# 2_MCU.net
KiCad netlist of a schematic drawn in Altium Designer
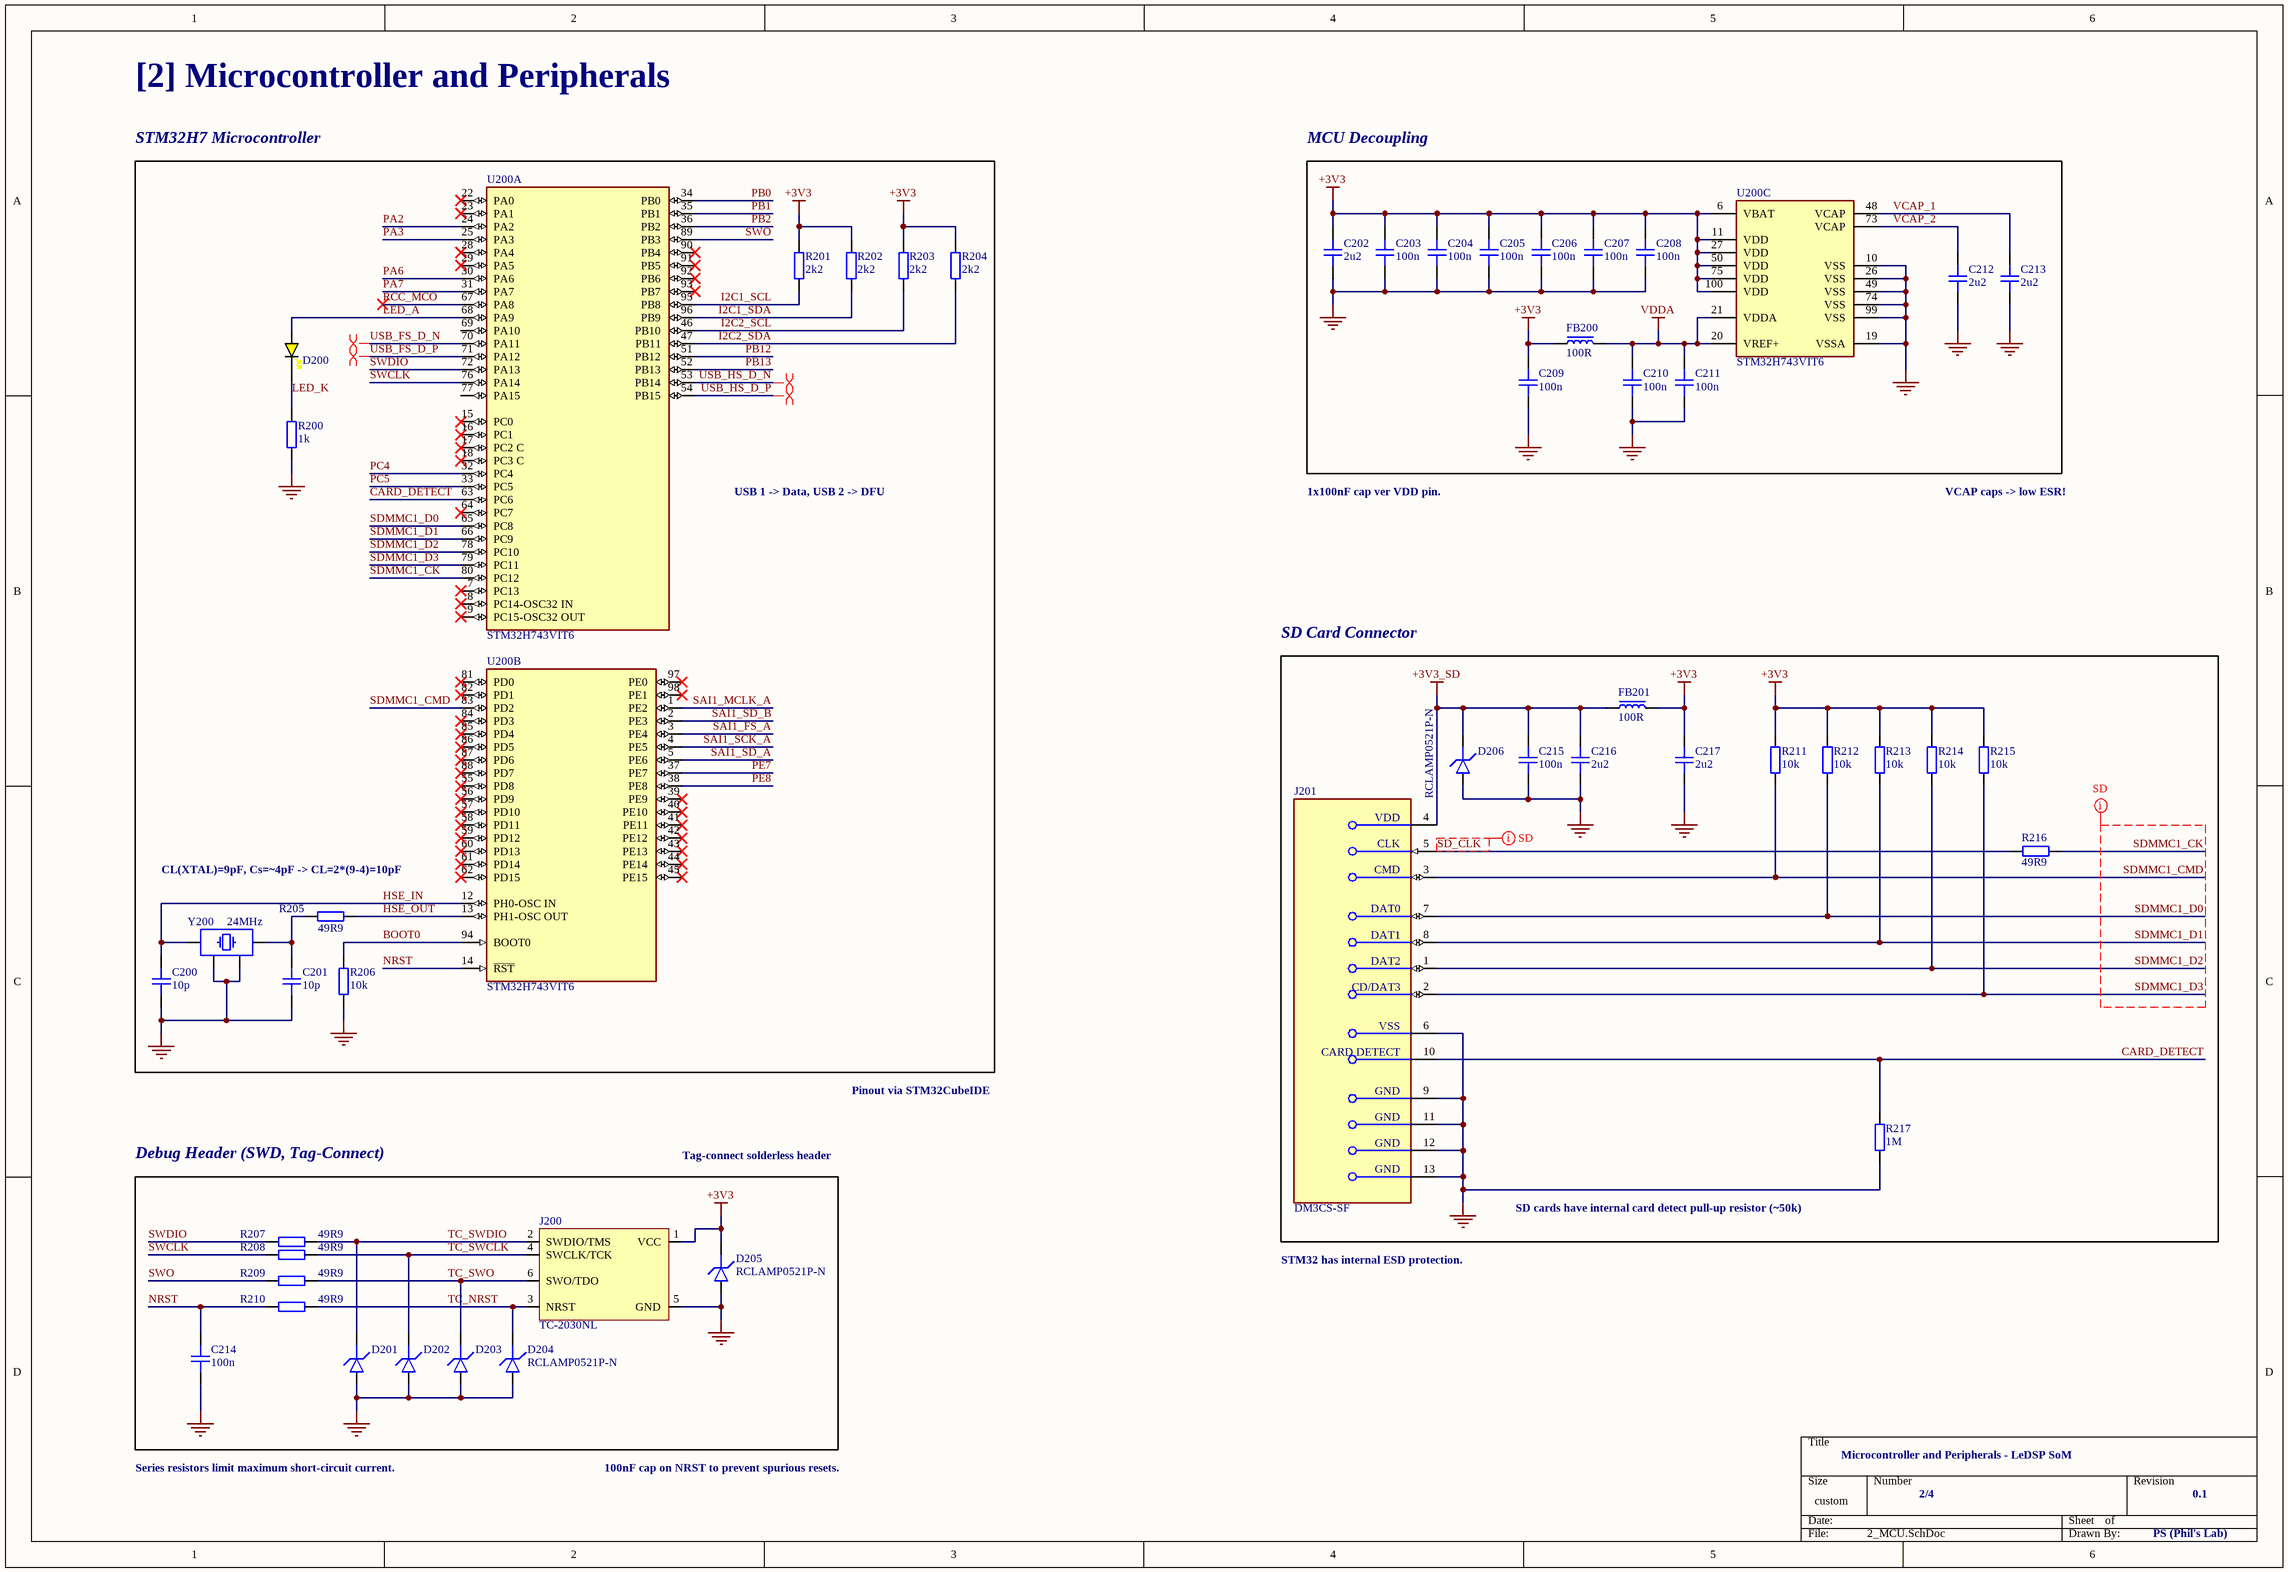
[diagram p0: 2_MCU.SchDoc]

(export (version "E")
  (design (tool "Eeschema 10.0.6"))
  (components
    (comp (ref "C200")
      (value "10p")
      (footprint "CAP_0402")
      (description "Capacitor SMD 0402 16V")
      (libsource (lib "Schematic-Lib-PhilsLab") (part "CAP_0402_16V"))
    )
    (comp (ref "C201")
      (value "10p")
      (footprint "CAP_0402")
      (description "Capacitor SMD 0402 16V")
      (libsource (lib "Schematic-Lib-PhilsLab") (part "CAP_0402_16V"))
    )
    (comp (ref "C202")
      (value "2u2")
      (footprint "CAP_0603")
      (description "Capacitor SMD 0603 16V")
      (libsource (lib "Schematic-Lib-PhilsLab") (part "CAP_0603_16V"))
    )
    (comp (ref "C203")
      (value "100n")
      (footprint "CAP_0402")
      (description "Capacitor SMD 0402 16V")
      (libsource (lib "Schematic-Lib-PhilsLab") (part "CAP_0402_16V"))
    )
    (comp (ref "C204")
      (value "100n")
      (footprint "CAP_0402")
      (description "Capacitor SMD 0402 16V")
      (libsource (lib "Schematic-Lib-PhilsLab") (part "CAP_0402_16V"))
    )
    (comp (ref "C205")
      (value "100n")
      (footprint "CAP_0402")
      (description "Capacitor SMD 0402 16V")
      (libsource (lib "Schematic-Lib-PhilsLab") (part "CAP_0402_16V"))
    )
    (comp (ref "C206")
      (value "100n")
      (footprint "CAP_0402")
      (description "Capacitor SMD 0402 16V")
      (libsource (lib "Schematic-Lib-PhilsLab") (part "CAP_0402_16V"))
    )
    (comp (ref "C207")
      (value "100n")
      (footprint "CAP_0402")
      (description "Capacitor SMD 0402 16V")
      (libsource (lib "Schematic-Lib-PhilsLab") (part "CAP_0402_16V"))
    )
    (comp (ref "C208")
      (value "100n")
      (footprint "CAP_0402")
      (description "Capacitor SMD 0402 16V")
      (libsource (lib "Schematic-Lib-PhilsLab") (part "CAP_0402_16V"))
    )
    (comp (ref "C209")
      (value "100n")
      (footprint "CAP_0402")
      (description "Capacitor SMD 0402 16V")
      (libsource (lib "Schematic-Lib-PhilsLab") (part "CAP_0402_16V"))
    )
    (comp (ref "C210")
      (value "100n")
      (footprint "CAP_0402")
      (description "Capacitor SMD 0402 16V")
      (libsource (lib "Schematic-Lib-PhilsLab") (part "CAP_0402_16V"))
    )
    (comp (ref "C211")
      (value "100n")
      (footprint "CAP_0402")
      (description "Capacitor SMD 0402 16V")
      (libsource (lib "Schematic-Lib-PhilsLab") (part "CAP_0402_16V"))
    )
    (comp (ref "C212")
      (value "2u2")
      (footprint "CAP_0402")
      (description "Capacitor SMD 0402 16V")
      (libsource (lib "Schematic-Lib-PhilsLab") (part "CAP_0402_16V"))
    )
    (comp (ref "C213")
      (value "2u2")
      (footprint "CAP_0402")
      (description "Capacitor SMD 0402 16V")
      (libsource (lib "Schematic-Lib-PhilsLab") (part "CAP_0402_16V"))
    )
    (comp (ref "C214")
      (value "100n")
      (footprint "CAP_0402")
      (description "Capacitor SMD 0402 16V")
      (libsource (lib "Schematic-Lib-PhilsLab") (part "CAP_0402_16V"))
    )
    (comp (ref "C215")
      (value "100n")
      (footprint "CAP_0402")
      (description "Capacitor SMD 0402 16V")
      (libsource (lib "Schematic-Lib-PhilsLab") (part "CAP_0402_16V"))
    )
    (comp (ref "C216")
      (value "2u2")
      (footprint "CAP_0603")
      (description "Capacitor SMD 0603 16V")
      (libsource (lib "Schematic-Lib-PhilsLab") (part "CAP_0603_16V"))
    )
    (comp (ref "C217")
      (value "2u2")
      (footprint "CAP_0603")
      (description "Capacitor SMD 0603 16V")
      (libsource (lib "Schematic-Lib-PhilsLab") (part "CAP_0603_16V"))
    )
    (comp (ref "D200")
      (value "YELLOW")
      (footprint "LED_0402_YELLOW")
      (description "LED 0402 YELLOW SMD")
      (libsource (lib "Schematic-Lib-PhilsLab") (part "LED_0402_YELLOW"))
    )
    (comp (ref "D201")
      (value "RCLAMP0521P-N")
      (footprint "D_0402")
      (description "Diode TVS / ESD 0402")
      (libsource (lib "Schematic-Lib-PhilsLab") (part "D_TVS_0402"))
    )
    (comp (ref "D202")
      (value "RCLAMP0521P-N")
      (footprint "D_0402")
      (description "Diode TVS / ESD 0402")
      (libsource (lib "Schematic-Lib-PhilsLab") (part "D_TVS_0402"))
    )
    (comp (ref "D203")
      (value "RCLAMP0521P-N")
      (footprint "D_0402")
      (description "Diode TVS / ESD 0402")
      (libsource (lib "Schematic-Lib-PhilsLab") (part "D_TVS_0402"))
    )
    (comp (ref "D204")
      (value "RCLAMP0521P-N")
      (footprint "D_0402")
      (description "Diode TVS / ESD 0402")
      (libsource (lib "Schematic-Lib-PhilsLab") (part "D_TVS_0402"))
    )
    (comp (ref "D205")
      (value "RCLAMP0521P-N")
      (footprint "D_0402")
      (description "Diode TVS / ESD 0402")
      (libsource (lib "Schematic-Lib-PhilsLab") (part "D_TVS_0402"))
    )
    (comp (ref "D206")
      (value "RCLAMP0521P-N")
      (footprint "D_0402")
      (description "Diode TVS / ESD 0402")
      (libsource (lib "Schematic-Lib-PhilsLab") (part "D_TVS_0402"))
    )
    (comp (ref "FB200")
      (value "100R")
      (footprint "FB_0603")
      (description "Ferrite Bead SMD 0603")
      (libsource (lib "Schematic-Lib-PhilsLab") (part "FB_0603"))
    )
    (comp (ref "FB201")
      (value "100R")
      (footprint "FB_0603")
      (description "Ferrite Bead SMD 0603")
      (libsource (lib "Schematic-Lib-PhilsLab") (part "FB_0603"))
    )
    (comp (ref "J200")
      (value "TC-2030NL")
      (footprint "TC2030-NL-FP")
      (description "Tag-Connect No-Solder SWD Debug Connector (No Legs) DO NOT PLACE")
      (fields (field (name "MANUFACTURER") "Tag-Connect"))
      (libsource (lib "Schematic-Lib-PhilsLab") (part "TC2030-NL"))
    )
    (comp (ref "J201")
      (value "DM3CS-SF")
      (footprint "FP-DM3CS-SF-MFG")
      (description "CONN MICRO SD CARD HINGED TYPE")
      (libsource (lib "Altium Content Vault") (part "bac915de5305cfdd1ca301aae530106"))
    )
    (comp (ref "R200")
      (value "1k")
      (footprint "RES_0402")
      (description "Resistor SMD 0402")
      (libsource (lib "Schematic-Lib-PhilsLab") (part "RES_0402"))
    )
    (comp (ref "R201")
      (value "2k2")
      (footprint "RES_0402")
      (description "Resistor SMD 0402")
      (libsource (lib "Schematic-Lib-PhilsLab") (part "RES_0402"))
    )
    (comp (ref "R202")
      (value "2k2")
      (footprint "RES_0402")
      (description "Resistor SMD 0402")
      (libsource (lib "Schematic-Lib-PhilsLab") (part "RES_0402"))
    )
    (comp (ref "R203")
      (value "2k2")
      (footprint "RES_0402")
      (description "Resistor SMD 0402")
      (libsource (lib "Schematic-Lib-PhilsLab") (part "RES_0402"))
    )
    (comp (ref "R204")
      (value "2k2")
      (footprint "RES_0402")
      (description "Resistor SMD 0402")
      (libsource (lib "Schematic-Lib-PhilsLab") (part "RES_0402"))
    )
    (comp (ref "R205")
      (value "49R9")
      (footprint "RES_0402")
      (description "Resistor SMD 0402")
      (libsource (lib "Schematic-Lib-PhilsLab") (part "RES_0402"))
    )
    (comp (ref "R206")
      (value "10k")
      (footprint "RES_0402")
      (description "Resistor SMD 0402")
      (libsource (lib "Schematic-Lib-PhilsLab") (part "RES_0402"))
    )
    (comp (ref "R207")
      (value "49R9")
      (footprint "RES_0402")
      (description "Resistor SMD 0402")
      (libsource (lib "Schematic-Lib-PhilsLab") (part "RES_0402"))
    )
    (comp (ref "R208")
      (value "49R9")
      (footprint "RES_0402")
      (description "Resistor SMD 0402")
      (libsource (lib "Schematic-Lib-PhilsLab") (part "RES_0402"))
    )
    (comp (ref "R209")
      (value "49R9")
      (footprint "RES_0402")
      (description "Resistor SMD 0402")
      (libsource (lib "Schematic-Lib-PhilsLab") (part "RES_0402"))
    )
    (comp (ref "R210")
      (value "49R9")
      (footprint "RES_0402")
      (description "Resistor SMD 0402")
      (libsource (lib "Schematic-Lib-PhilsLab") (part "RES_0402"))
    )
    (comp (ref "R211")
      (value "10k")
      (footprint "RES_0402")
      (description "Resistor SMD 0402")
      (libsource (lib "Schematic-Lib-PhilsLab") (part "RES_0402"))
    )
    (comp (ref "R212")
      (value "10k")
      (footprint "RES_0402")
      (description "Resistor SMD 0402")
      (libsource (lib "Schematic-Lib-PhilsLab") (part "RES_0402"))
    )
    (comp (ref "R213")
      (value "10k")
      (footprint "RES_0402")
      (description "Resistor SMD 0402")
      (libsource (lib "Schematic-Lib-PhilsLab") (part "RES_0402"))
    )
    (comp (ref "R214")
      (value "10k")
      (footprint "RES_0402")
      (description "Resistor SMD 0402")
      (libsource (lib "Schematic-Lib-PhilsLab") (part "RES_0402"))
    )
    (comp (ref "R215")
      (value "10k")
      (footprint "RES_0402")
      (description "Resistor SMD 0402")
      (libsource (lib "Schematic-Lib-PhilsLab") (part "RES_0402"))
    )
    (comp (ref "R216")
      (value "49R9")
      (footprint "RES_0402")
      (description "Resistor SMD 0402")
      (libsource (lib "Schematic-Lib-PhilsLab") (part "RES_0402"))
    )
    (comp (ref "R217")
      (value "1M")
      (footprint "RES_0402")
      (description "Resistor SMD 0402")
      (libsource (lib "Schematic-Lib-PhilsLab") (part "RES_0402"))
    )
    (comp (ref "U200")
      (value "STM32H743VIT6")
      (footprint "FP-LQFP100-1L-MFG")
      (description "IC MCU 32BIT 2MB FLASH 100LQFP")
      (fields
        (field (name "OCTOPART") "https://octopart.com/stm32h743vit6-stmicroelectronics-76372527")
        (field (name "MANUFACTURER") "STMicroelectronics")
      )
      (libsource (lib "Altium Content Vault") (part "01082ce2885d1d16a22823c45526fe6"))
    )
    (comp (ref "Y200")
      (value "24MHz")
      (footprint "XTAL_3225")
      (description "Crystal SMD 24MHz 10PPM 7pF 3225")
      (fields (field (name "MANUFACTURER") "Epson"))
      (libsource (lib "Schematic-Lib-PhilsLab") (part "TSX-3225_24.0000MF15X-AC"))
    )
  )
  (nets
    (net (code "1") (name "+3V3") (class "Default")
      (node (ref "C202") (pin "2") (pinfunction "2_2") (pintype "passive"))
      (node (ref "C203") (pin "2") (pinfunction "2_2") (pintype "passive"))
      (node (ref "C204") (pin "2") (pinfunction "2_2") (pintype "passive"))
      (node (ref "C205") (pin "2") (pinfunction "2_2") (pintype "passive"))
      (node (ref "C206") (pin "2") (pinfunction "2_2") (pintype "passive"))
      (node (ref "C207") (pin "2") (pinfunction "2_2") (pintype "passive"))
      (node (ref "C208") (pin "2") (pinfunction "2_2") (pintype "passive"))
      (node (ref "C209") (pin "2") (pinfunction "2_2") (pintype "passive"))
      (node (ref "C217") (pin "2") (pinfunction "2_2") (pintype "passive"))
      (node (ref "D205") (pin "K") (pinfunction "K_K") (pintype "passive"))
      (node (ref "FB200") (pin "1") (pinfunction "1_1") (pintype "passive"))
      (node (ref "FB201") (pin "2") (pinfunction "2_2") (pintype "passive"))
      (node (ref "J200") (pin "1") (pinfunction "VCC_1") (pintype "passive"))
      (node (ref "R201") (pin "2") (pinfunction "2_2") (pintype "passive"))
      (node (ref "R202") (pin "2") (pinfunction "2_2") (pintype "passive"))
      (node (ref "R203") (pin "2") (pinfunction "2_2") (pintype "passive"))
      (node (ref "R204") (pin "2") (pinfunction "2_2") (pintype "passive"))
      (node (ref "R211") (pin "2") (pinfunction "2_2") (pintype "passive"))
      (node (ref "R212") (pin "2") (pinfunction "2_2") (pintype "passive"))
      (node (ref "R213") (pin "2") (pinfunction "2_2") (pintype "passive"))
      (node (ref "R214") (pin "2") (pinfunction "2_2") (pintype "passive"))
      (node (ref "R215") (pin "2") (pinfunction "2_2") (pintype "passive"))
      (node (ref "U200") (pin "100") (pinfunction "VDD_100") (pintype "power_in"))
      (node (ref "U200") (pin "11") (pinfunction "VDD_11") (pintype "power_in"))
      (node (ref "U200") (pin "27") (pinfunction "VDD_27") (pintype "power_in"))
      (node (ref "U200") (pin "50") (pinfunction "VDD_50") (pintype "power_in"))
      (node (ref "U200") (pin "6") (pinfunction "VBAT_6") (pintype "power_in"))
      (node (ref "U200") (pin "75") (pinfunction "VDD_75") (pintype "power_in"))
    )
    (net (code "2") (name "+3V3_SD") (class "Default")
      (node (ref "C215") (pin "2") (pinfunction "2_2") (pintype "passive"))
      (node (ref "C216") (pin "2") (pinfunction "2_2") (pintype "passive"))
      (node (ref "D206") (pin "K") (pinfunction "K_K") (pintype "passive"))
      (node (ref "FB201") (pin "1") (pinfunction "1_1") (pintype "passive"))
      (node (ref "J201") (pin "4") (pinfunction "VDD_4") (pintype "power_in"))
    )
    (net (code "3") (name "/BOOT0") (class "Default")
      (node (ref "R206") (pin "2") (pinfunction "2_2") (pintype "passive"))
      (node (ref "U200") (pin "94") (pinfunction "BOOT0_94") (pintype "input"))
    )
    (net (code "4") (name "/CARD_DETECT") (class "Default")
      (node (ref "J201") (pin "10") (pinfunction "CARD_DETECT_10") (pintype "passive"))
      (node (ref "R217") (pin "2") (pinfunction "2_2") (pintype "passive"))
      (node (ref "U200") (pin "63") (pinfunction "PC6_63") (pintype "bidirectional"))
    )
    (net (code "5") (name "/HSE_IN") (class "Default")
      (node (ref "C200") (pin "2") (pinfunction "2_2") (pintype "passive"))
      (node (ref "U200") (pin "12") (pinfunction "PH0-OSC_IN_12") (pintype "bidirectional"))
      (node (ref "Y200") (pin "1") (pinfunction "1_1") (pintype "passive"))
    )
    (net (code "6") (name "/HSE_OUT") (class "Default")
      (node (ref "R205") (pin "2") (pinfunction "2_2") (pintype "passive"))
      (node (ref "U200") (pin "13") (pinfunction "PH1-OSC_OUT_13") (pintype "bidirectional"))
    )
    (net (code "7") (name "/I2C1_SCL") (class "Default")
      (node (ref "R201") (pin "1") (pinfunction "1_1") (pintype "passive"))
      (node (ref "U200") (pin "95") (pinfunction "PB8_95") (pintype "bidirectional"))
    )
    (net (code "8") (name "/I2C1_SDA") (class "Default")
      (node (ref "R202") (pin "1") (pinfunction "1_1") (pintype "passive"))
      (node (ref "U200") (pin "96") (pinfunction "PB9_96") (pintype "bidirectional"))
    )
    (net (code "9") (name "/I2C2_SCL") (class "Default")
      (node (ref "R203") (pin "1") (pinfunction "1_1") (pintype "passive"))
      (node (ref "U200") (pin "46") (pinfunction "PB10_46") (pintype "bidirectional"))
    )
    (net (code "10") (name "/I2C2_SDA") (class "Default")
      (node (ref "R204") (pin "1") (pinfunction "1_1") (pintype "passive"))
      (node (ref "U200") (pin "47") (pinfunction "PB11_47") (pintype "bidirectional"))
    )
    (net (code "11") (name "/LED_A") (class "Default")
      (node (ref "D200") (pin "A") (pinfunction "A_A") (pintype "passive"))
      (node (ref "U200") (pin "68") (pinfunction "PA9_68") (pintype "bidirectional"))
    )
    (net (code "12") (name "/LED_K") (class "Default")
      (node (ref "D200") (pin "K") (pinfunction "K_K") (pintype "passive"))
      (node (ref "R200") (pin "2") (pinfunction "2_2") (pintype "passive"))
    )
    (net (code "13") (name "/NRST") (class "Default")
      (node (ref "C214") (pin "2") (pinfunction "2_2") (pintype "passive"))
      (node (ref "R210") (pin "1") (pinfunction "1_1") (pintype "passive"))
      (node (ref "U200") (pin "14") (pinfunction "~{RST}_14") (pintype "input"))
    )
    (net (code "14") (name "/PA2") (class "Default")
      (node (ref "U200") (pin "24") (pinfunction "PA2_24") (pintype "bidirectional"))
    )
    (net (code "15") (name "/PA3") (class "Default")
      (node (ref "U200") (pin "25") (pinfunction "PA3_25") (pintype "bidirectional"))
    )
    (net (code "16") (name "/PA6") (class "Default")
      (node (ref "U200") (pin "30") (pinfunction "PA6_30") (pintype "bidirectional"))
    )
    (net (code "17") (name "/PA7") (class "Default")
      (node (ref "U200") (pin "31") (pinfunction "PA7_31") (pintype "bidirectional"))
    )
    (net (code "18") (name "/PB0") (class "Default")
      (node (ref "U200") (pin "34") (pinfunction "PB0_34") (pintype "bidirectional"))
    )
    (net (code "19") (name "/PB1") (class "Default")
      (node (ref "U200") (pin "35") (pinfunction "PB1_35") (pintype "bidirectional"))
    )
    (net (code "20") (name "/PB2") (class "Default")
      (node (ref "U200") (pin "36") (pinfunction "PB2_36") (pintype "bidirectional"))
    )
    (net (code "21") (name "/PB12") (class "Default")
      (node (ref "U200") (pin "51") (pinfunction "PB12_51") (pintype "bidirectional"))
    )
    (net (code "22") (name "/PB13") (class "Default")
      (node (ref "U200") (pin "52") (pinfunction "PB13_52") (pintype "bidirectional"))
    )
    (net (code "23") (name "/PC4") (class "Default")
      (node (ref "U200") (pin "32") (pinfunction "PC4_32") (pintype "bidirectional"))
    )
    (net (code "24") (name "/PC5") (class "Default")
      (node (ref "U200") (pin "33") (pinfunction "PC5_33") (pintype "bidirectional"))
    )
    (net (code "25") (name "/PE7") (class "Default")
      (node (ref "U200") (pin "37") (pinfunction "PE7_37") (pintype "bidirectional"))
    )
    (net (code "26") (name "/PE8") (class "Default")
      (node (ref "U200") (pin "38") (pinfunction "PE8_38") (pintype "bidirectional"))
    )
    (net (code "27") (name "/RCC_MCO") (class "Default")
      (node (ref "U200") (pin "67") (pinfunction "PA8_67") (pintype "bidirectional+no_connect"))
    )
    (net (code "28") (name "/SAI1_FS_A") (class "Default")
      (node (ref "U200") (pin "3") (pinfunction "PE4_3") (pintype "bidirectional"))
    )
    (net (code "29") (name "/SAI1_MCLK_A") (class "Default")
      (node (ref "U200") (pin "1") (pinfunction "PE2_1") (pintype "bidirectional"))
    )
    (net (code "30") (name "/SAI1_SCK_A") (class "Default")
      (node (ref "U200") (pin "4") (pinfunction "PE5_4") (pintype "bidirectional"))
    )
    (net (code "31") (name "/SAI1_SD_A") (class "Default")
      (node (ref "U200") (pin "5") (pinfunction "PE6_5") (pintype "bidirectional"))
    )
    (net (code "32") (name "/SAI1_SD_B") (class "Default")
      (node (ref "U200") (pin "2") (pinfunction "PE3_2") (pintype "bidirectional"))
    )
    (net (code "33") (name "/SDMMC1_CK") (class "Default")
      (node (ref "R216") (pin "2") (pinfunction "2_2") (pintype "passive"))
      (node (ref "U200") (pin "80") (pinfunction "PC12_80") (pintype "bidirectional"))
    )
    (net (code "34") (name "/SDMMC1_CMD") (class "Default")
      (node (ref "J201") (pin "3") (pinfunction "CMD_3") (pintype "bidirectional"))
      (node (ref "R211") (pin "1") (pinfunction "1_1") (pintype "passive"))
      (node (ref "U200") (pin "83") (pinfunction "PD2_83") (pintype "bidirectional"))
    )
    (net (code "35") (name "/SDMMC1_D0") (class "Default")
      (node (ref "J201") (pin "7") (pinfunction "DAT0_7") (pintype "bidirectional"))
      (node (ref "R212") (pin "1") (pinfunction "1_1") (pintype "passive"))
      (node (ref "U200") (pin "65") (pinfunction "PC8_65") (pintype "bidirectional"))
    )
    (net (code "36") (name "/SDMMC1_D1") (class "Default")
      (node (ref "J201") (pin "8") (pinfunction "DAT1_8") (pintype "bidirectional"))
      (node (ref "R213") (pin "1") (pinfunction "1_1") (pintype "passive"))
      (node (ref "U200") (pin "66") (pinfunction "PC9_66") (pintype "bidirectional"))
    )
    (net (code "37") (name "/SDMMC1_D2") (class "Default")
      (node (ref "J201") (pin "1") (pinfunction "DAT2_1") (pintype "bidirectional"))
      (node (ref "R214") (pin "1") (pinfunction "1_1") (pintype "passive"))
      (node (ref "U200") (pin "78") (pinfunction "PC10_78") (pintype "bidirectional"))
    )
    (net (code "38") (name "/SDMMC1_D3") (class "Default")
      (node (ref "J201") (pin "2") (pinfunction "CD/DAT3_2") (pintype "bidirectional"))
      (node (ref "R215") (pin "1") (pinfunction "1_1") (pintype "passive"))
      (node (ref "U200") (pin "79") (pinfunction "PC11_79") (pintype "bidirectional"))
    )
    (net (code "39") (name "/SD_CLK") (class "Default")
      (node (ref "J201") (pin "5") (pinfunction "CLK_5") (pintype "input"))
      (node (ref "R216") (pin "1") (pinfunction "1_1") (pintype "passive"))
    )
    (net (code "40") (name "/SWCLK") (class "Default")
      (node (ref "R208") (pin "1") (pinfunction "1_1") (pintype "passive"))
      (node (ref "U200") (pin "76") (pinfunction "PA14_76") (pintype "bidirectional"))
    )
    (net (code "41") (name "/SWDIO") (class "Default")
      (node (ref "R207") (pin "1") (pinfunction "1_1") (pintype "passive"))
      (node (ref "U200") (pin "72") (pinfunction "PA13_72") (pintype "bidirectional"))
    )
    (net (code "42") (name "/SWO") (class "Default")
      (node (ref "R209") (pin "1") (pinfunction "1_1") (pintype "passive"))
      (node (ref "U200") (pin "89") (pinfunction "PB3_89") (pintype "bidirectional"))
    )
    (net (code "43") (name "/TC_NRST") (class "Default")
      (node (ref "D204") (pin "K") (pinfunction "K_K") (pintype "passive"))
      (node (ref "J200") (pin "3") (pinfunction "NRST_3") (pintype "passive"))
      (node (ref "R210") (pin "2") (pinfunction "2_2") (pintype "passive"))
    )
    (net (code "44") (name "/TC_SWCLK") (class "Default")
      (node (ref "D202") (pin "K") (pinfunction "K_K") (pintype "passive"))
      (node (ref "J200") (pin "4") (pinfunction "SWCLK/TCK_4") (pintype "passive"))
      (node (ref "R208") (pin "2") (pinfunction "2_2") (pintype "passive"))
    )
    (net (code "45") (name "/TC_SWDIO") (class "Default")
      (node (ref "D201") (pin "K") (pinfunction "K_K") (pintype "passive"))
      (node (ref "J200") (pin "2") (pinfunction "SWDIO/TMS_2") (pintype "passive"))
      (node (ref "R207") (pin "2") (pinfunction "2_2") (pintype "passive"))
    )
    (net (code "46") (name "/TC_SWO") (class "Default")
      (node (ref "D203") (pin "K") (pinfunction "K_K") (pintype "passive"))
      (node (ref "J200") (pin "6") (pinfunction "SWO/TDO_6") (pintype "passive"))
      (node (ref "R209") (pin "2") (pinfunction "2_2") (pintype "passive"))
    )
    (net (code "47") (name "/USB_FS_D_N") (class "Default")
      (node (ref "U200") (pin "70") (pinfunction "PA11_70") (pintype "bidirectional"))
    )
    (net (code "48") (name "/USB_FS_D_P") (class "Default")
      (node (ref "U200") (pin "71") (pinfunction "PA12_71") (pintype "bidirectional"))
    )
    (net (code "49") (name "/USB_HS_D_N") (class "Default")
      (node (ref "U200") (pin "53") (pinfunction "PB14_53") (pintype "bidirectional"))
    )
    (net (code "50") (name "/USB_HS_D_P") (class "Default")
      (node (ref "U200") (pin "54") (pinfunction "PB15_54") (pintype "bidirectional"))
    )
    (net (code "51") (name "/VCAP_1") (class "Default")
      (node (ref "C213") (pin "2") (pinfunction "2_2") (pintype "passive"))
      (node (ref "U200") (pin "48") (pinfunction "VCAP_48") (pintype "passive"))
    )
    (net (code "52") (name "/VCAP_2") (class "Default")
      (node (ref "C212") (pin "2") (pinfunction "2_2") (pintype "passive"))
      (node (ref "U200") (pin "73") (pinfunction "VCAP_73") (pintype "passive"))
    )
    (net (code "53") (name "GND") (class "Default")
      (node (ref "C200") (pin "1") (pinfunction "1_1") (pintype "passive"))
      (node (ref "C201") (pin "1") (pinfunction "1_1") (pintype "passive"))
      (node (ref "C202") (pin "1") (pinfunction "1_1") (pintype "passive"))
      (node (ref "C203") (pin "1") (pinfunction "1_1") (pintype "passive"))
      (node (ref "C204") (pin "1") (pinfunction "1_1") (pintype "passive"))
      (node (ref "C205") (pin "1") (pinfunction "1_1") (pintype "passive"))
      (node (ref "C206") (pin "1") (pinfunction "1_1") (pintype "passive"))
      (node (ref "C207") (pin "1") (pinfunction "1_1") (pintype "passive"))
      (node (ref "C208") (pin "1") (pinfunction "1_1") (pintype "passive"))
      (node (ref "C209") (pin "1") (pinfunction "1_1") (pintype "passive"))
      (node (ref "C210") (pin "1") (pinfunction "1_1") (pintype "passive"))
      (node (ref "C211") (pin "1") (pinfunction "1_1") (pintype "passive"))
      (node (ref "C212") (pin "1") (pinfunction "1_1") (pintype "passive"))
      (node (ref "C213") (pin "1") (pinfunction "1_1") (pintype "passive"))
      (node (ref "C214") (pin "1") (pinfunction "1_1") (pintype "passive"))
      (node (ref "C215") (pin "1") (pinfunction "1_1") (pintype "passive"))
      (node (ref "C216") (pin "1") (pinfunction "1_1") (pintype "passive"))
      (node (ref "C217") (pin "1") (pinfunction "1_1") (pintype "passive"))
      (node (ref "D201") (pin "A") (pinfunction "A_A") (pintype "passive"))
      (node (ref "D202") (pin "A") (pinfunction "A_A") (pintype "passive"))
      (node (ref "D203") (pin "A") (pinfunction "A_A") (pintype "passive"))
      (node (ref "D204") (pin "A") (pinfunction "A_A") (pintype "passive"))
      (node (ref "D205") (pin "A") (pinfunction "A_A") (pintype "passive"))
      (node (ref "D206") (pin "A") (pinfunction "A_A") (pintype "passive"))
      (node (ref "J200") (pin "5") (pinfunction "GND_5") (pintype "passive"))
      (node (ref "J201") (pin "11") (pinfunction "GND_11") (pintype "power_in"))
      (node (ref "J201") (pin "12") (pinfunction "GND_12") (pintype "power_in"))
      (node (ref "J201") (pin "13") (pinfunction "GND_13") (pintype "power_in"))
      (node (ref "J201") (pin "6") (pinfunction "VSS_6") (pintype "power_in"))
      (node (ref "J201") (pin "9") (pinfunction "GND_9") (pintype "power_in"))
      (node (ref "R200") (pin "1") (pinfunction "1_1") (pintype "passive"))
      (node (ref "R206") (pin "1") (pinfunction "1_1") (pintype "passive"))
      (node (ref "R217") (pin "1") (pinfunction "1_1") (pintype "passive"))
      (node (ref "U200") (pin "10") (pinfunction "VSS_10") (pintype "power_in"))
      (node (ref "U200") (pin "19") (pinfunction "VSSA_19") (pintype "power_in"))
      (node (ref "U200") (pin "26") (pinfunction "VSS_26") (pintype "power_in"))
      (node (ref "U200") (pin "49") (pinfunction "VSS_49") (pintype "power_in"))
      (node (ref "U200") (pin "74") (pinfunction "VSS_74") (pintype "power_in"))
      (node (ref "U200") (pin "99") (pinfunction "VSS_99") (pintype "power_in"))
      (node (ref "Y200") (pin "2") (pinfunction "2_2") (pintype "passive"))
      (node (ref "Y200") (pin "4") (pinfunction "4_4") (pintype "passive"))
    )
    (net (code "54") (name "Net-(C201-Pad2)") (class "Default")
      (node (ref "C201") (pin "2") (pinfunction "2_2") (pintype "passive"))
      (node (ref "R205") (pin "1") (pinfunction "1_1") (pintype "passive"))
      (node (ref "Y200") (pin "3") (pinfunction "3_3") (pintype "passive"))
    )
    (net (code "55") (name "VDDA") (class "Default")
      (node (ref "C210") (pin "2") (pinfunction "2_2") (pintype "passive"))
      (node (ref "C211") (pin "2") (pinfunction "2_2") (pintype "passive"))
      (node (ref "FB200") (pin "2") (pinfunction "2_2") (pintype "passive"))
      (node (ref "U200") (pin "20") (pinfunction "VREF+_20") (pintype "power_in"))
      (node (ref "U200") (pin "21") (pinfunction "VDDA_21") (pintype "power_in"))
    )
    (net (code "56") (name "unconnected-(U200A-PA0-Pad22)") (class "Default")
      (node (ref "U200") (pin "22") (pinfunction "PA0_22") (pintype "bidirectional+no_connect"))
    )
    (net (code "57") (name "unconnected-(U200A-PA1-Pad23)") (class "Default")
      (node (ref "U200") (pin "23") (pinfunction "PA1_23") (pintype "bidirectional+no_connect"))
    )
    (net (code "58") (name "unconnected-(U200A-PA4-Pad28)") (class "Default")
      (node (ref "U200") (pin "28") (pinfunction "PA4_28") (pintype "bidirectional+no_connect"))
    )
    (net (code "59") (name "unconnected-(U200A-PA5-Pad29)") (class "Default")
      (node (ref "U200") (pin "29") (pinfunction "PA5_29") (pintype "bidirectional+no_connect"))
    )
    (net (code "60") (name "unconnected-(U200A-PA10-Pad69)") (class "Default")
      (node (ref "U200") (pin "69") (pinfunction "PA10_69") (pintype "bidirectional"))
    )
    (net (code "61") (name "unconnected-(U200A-PA15-Pad77)") (class "Default")
      (node (ref "U200") (pin "77") (pinfunction "PA15_77") (pintype "bidirectional"))
    )
    (net (code "62") (name "unconnected-(U200A-PB4-Pad90)") (class "Default")
      (node (ref "U200") (pin "90") (pinfunction "PB4_90") (pintype "bidirectional+no_connect"))
    )
    (net (code "63") (name "unconnected-(U200A-PB5-Pad91)") (class "Default")
      (node (ref "U200") (pin "91") (pinfunction "PB5_91") (pintype "bidirectional+no_connect"))
    )
    (net (code "64") (name "unconnected-(U200A-PB6-Pad92)") (class "Default")
      (node (ref "U200") (pin "92") (pinfunction "PB6_92") (pintype "bidirectional+no_connect"))
    )
    (net (code "65") (name "unconnected-(U200A-PB7-Pad93)") (class "Default")
      (node (ref "U200") (pin "93") (pinfunction "PB7_93") (pintype "bidirectional+no_connect"))
    )
    (net (code "66") (name "unconnected-(U200A-PC0-Pad15)") (class "Default")
      (node (ref "U200") (pin "15") (pinfunction "PC0_15") (pintype "bidirectional+no_connect"))
    )
    (net (code "67") (name "unconnected-(U200A-PC1-Pad16)") (class "Default")
      (node (ref "U200") (pin "16") (pinfunction "PC1_16") (pintype "bidirectional+no_connect"))
    )
    (net (code "68") (name "unconnected-(U200A-PC2_C-Pad17)") (class "Default")
      (node (ref "U200") (pin "17") (pinfunction "PC2_C_17") (pintype "bidirectional+no_connect"))
    )
    (net (code "69") (name "unconnected-(U200A-PC3_C-Pad18)") (class "Default")
      (node (ref "U200") (pin "18") (pinfunction "PC3_C_18") (pintype "bidirectional+no_connect"))
    )
    (net (code "70") (name "unconnected-(U200A-PC7-Pad64)") (class "Default")
      (node (ref "U200") (pin "64") (pinfunction "PC7_64") (pintype "bidirectional+no_connect"))
    )
    (net (code "71") (name "unconnected-(U200A-PC13-Pad7)") (class "Default")
      (node (ref "U200") (pin "7") (pinfunction "PC13_7") (pintype "bidirectional+no_connect"))
    )
    (net (code "72") (name "unconnected-(U200A-PC14-OSC32_IN-Pad8)") (class "Default")
      (node (ref "U200") (pin "8") (pinfunction "PC14-OSC32_IN_8") (pintype "bidirectional+no_connect"))
    )
    (net (code "73") (name "unconnected-(U200A-PC15-OSC32_OUT-Pad9)") (class "Default")
      (node (ref "U200") (pin "9") (pinfunction "PC15-OSC32_OUT_9") (pintype "bidirectional+no_connect"))
    )
    (net (code "74") (name "unconnected-(U200B-PD0-Pad81)") (class "Default")
      (node (ref "U200") (pin "81") (pinfunction "PD0_81") (pintype "bidirectional+no_connect"))
    )
    (net (code "75") (name "unconnected-(U200B-PD1-Pad82)") (class "Default")
      (node (ref "U200") (pin "82") (pinfunction "PD1_82") (pintype "bidirectional+no_connect"))
    )
    (net (code "76") (name "unconnected-(U200B-PD3-Pad84)") (class "Default")
      (node (ref "U200") (pin "84") (pinfunction "PD3_84") (pintype "bidirectional+no_connect"))
    )
    (net (code "77") (name "unconnected-(U200B-PD4-Pad85)") (class "Default")
      (node (ref "U200") (pin "85") (pinfunction "PD4_85") (pintype "bidirectional+no_connect"))
    )
    (net (code "78") (name "unconnected-(U200B-PD5-Pad86)") (class "Default")
      (node (ref "U200") (pin "86") (pinfunction "PD5_86") (pintype "bidirectional+no_connect"))
    )
    (net (code "79") (name "unconnected-(U200B-PD6-Pad87)") (class "Default")
      (node (ref "U200") (pin "87") (pinfunction "PD6_87") (pintype "bidirectional+no_connect"))
    )
    (net (code "80") (name "unconnected-(U200B-PD7-Pad88)") (class "Default")
      (node (ref "U200") (pin "88") (pinfunction "PD7_88") (pintype "bidirectional+no_connect"))
    )
    (net (code "81") (name "unconnected-(U200B-PD8-Pad55)") (class "Default")
      (node (ref "U200") (pin "55") (pinfunction "PD8_55") (pintype "bidirectional+no_connect"))
    )
    (net (code "82") (name "unconnected-(U200B-PD9-Pad56)") (class "Default")
      (node (ref "U200") (pin "56") (pinfunction "PD9_56") (pintype "bidirectional+no_connect"))
    )
    (net (code "83") (name "unconnected-(U200B-PD10-Pad57)") (class "Default")
      (node (ref "U200") (pin "57") (pinfunction "PD10_57") (pintype "bidirectional+no_connect"))
    )
    (net (code "84") (name "unconnected-(U200B-PD11-Pad58)") (class "Default")
      (node (ref "U200") (pin "58") (pinfunction "PD11_58") (pintype "bidirectional+no_connect"))
    )
    (net (code "85") (name "unconnected-(U200B-PD12-Pad59)") (class "Default")
      (node (ref "U200") (pin "59") (pinfunction "PD12_59") (pintype "bidirectional+no_connect"))
    )
    (net (code "86") (name "unconnected-(U200B-PD13-Pad60)") (class "Default")
      (node (ref "U200") (pin "60") (pinfunction "PD13_60") (pintype "bidirectional+no_connect"))
    )
    (net (code "87") (name "unconnected-(U200B-PD14-Pad61)") (class "Default")
      (node (ref "U200") (pin "61") (pinfunction "PD14_61") (pintype "bidirectional+no_connect"))
    )
    (net (code "88") (name "unconnected-(U200B-PD15-Pad62)") (class "Default")
      (node (ref "U200") (pin "62") (pinfunction "PD15_62") (pintype "bidirectional+no_connect"))
    )
    (net (code "89") (name "unconnected-(U200B-PE0-Pad97)") (class "Default")
      (node (ref "U200") (pin "97") (pinfunction "PE0_97") (pintype "bidirectional+no_connect"))
    )
    (net (code "90") (name "unconnected-(U200B-PE1-Pad98)") (class "Default")
      (node (ref "U200") (pin "98") (pinfunction "PE1_98") (pintype "bidirectional+no_connect"))
    )
    (net (code "91") (name "unconnected-(U200B-PE9-Pad39)") (class "Default")
      (node (ref "U200") (pin "39") (pinfunction "PE9_39") (pintype "bidirectional+no_connect"))
    )
    (net (code "92") (name "unconnected-(U200B-PE10-Pad40)") (class "Default")
      (node (ref "U200") (pin "40") (pinfunction "PE10_40") (pintype "bidirectional+no_connect"))
    )
    (net (code "93") (name "unconnected-(U200B-PE11-Pad41)") (class "Default")
      (node (ref "U200") (pin "41") (pinfunction "PE11_41") (pintype "bidirectional+no_connect"))
    )
    (net (code "94") (name "unconnected-(U200B-PE12-Pad42)") (class "Default")
      (node (ref "U200") (pin "42") (pinfunction "PE12_42") (pintype "bidirectional+no_connect"))
    )
    (net (code "95") (name "unconnected-(U200B-PE13-Pad43)") (class "Default")
      (node (ref "U200") (pin "43") (pinfunction "PE13_43") (pintype "bidirectional+no_connect"))
    )
    (net (code "96") (name "unconnected-(U200B-PE14-Pad44)") (class "Default")
      (node (ref "U200") (pin "44") (pinfunction "PE14_44") (pintype "bidirectional+no_connect"))
    )
    (net (code "97") (name "unconnected-(U200B-PE15-Pad45)") (class "Default")
      (node (ref "U200") (pin "45") (pinfunction "PE15_45") (pintype "bidirectional+no_connect"))
    )
  )
)
